# PowerSupply-5V-3_3V-v11-OtherMill.net
KiCad netlist of a schematic drawn in EAGLE
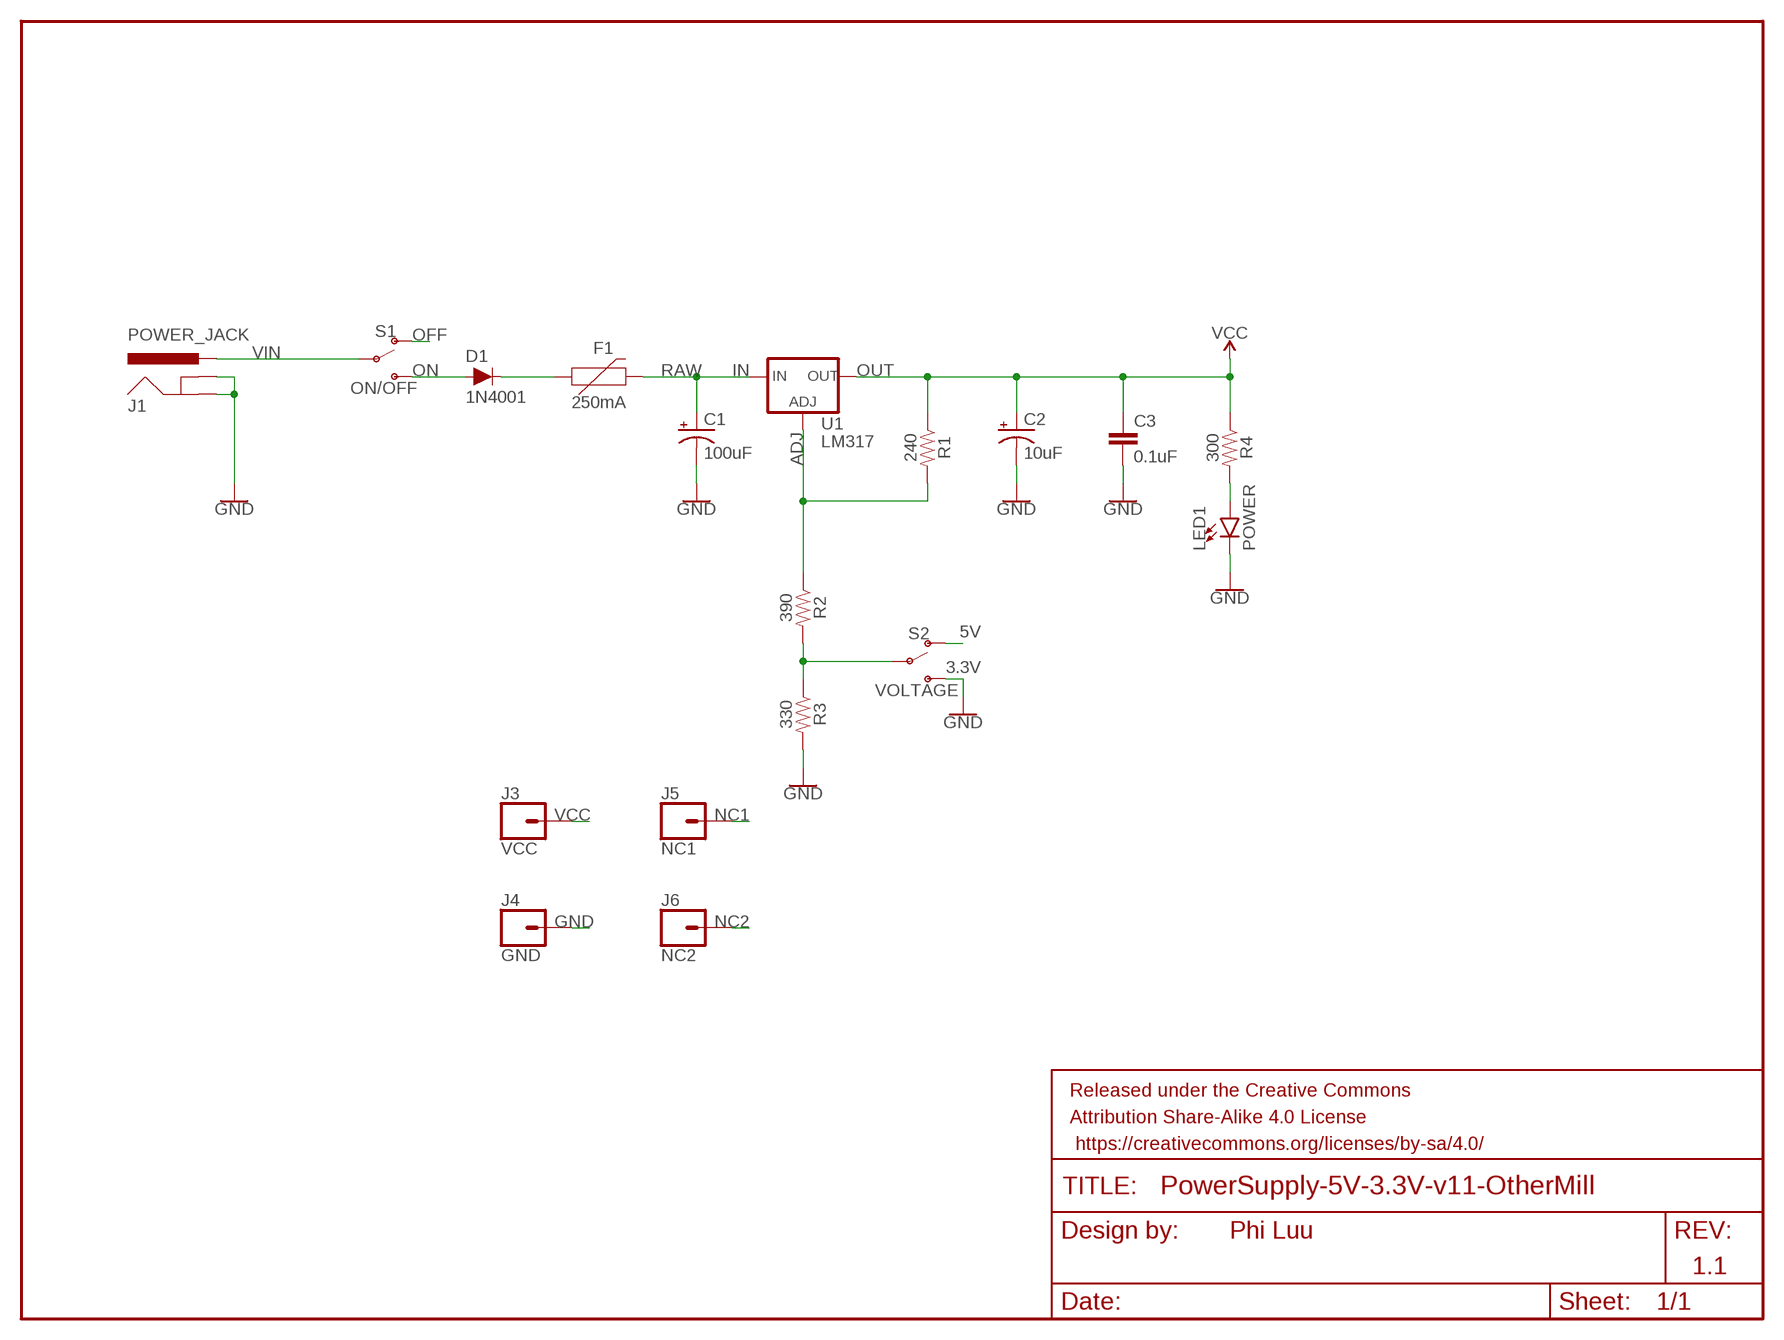
[diagram p0: schematic, sheet 1]

(export (version "E")
  (design (tool "Eeschema 10.0.6"))
  (components
    (comp (ref "C1")
      (value "100uF")
      (footprint "eagle-import:CPOL-RADIAL-2.5MM-6.5MM")
      (libsource (lib "eagle-import") (part "100UF-POLAR-RADIAL-2.5MM-25V-20%"))
    )
    (comp (ref "C2")
      (value "10uF")
      (footprint "eagle-import:CPOL-RADIAL-2.5MM-5MM")
      (libsource (lib "eagle-import") (part "10UF-POLAR-RADIAL-2.5MM-25V-20%"))
    )
    (comp (ref "C3")
      (value "0.1uF")
      (footprint "eagle-import:CAP-PTH-SMALL-KIT")
      (libsource (lib "eagle-import") (part "0.1UF-KIT-EZ-50V-20%"))
    )
    (comp (ref "D1")
      (value "1N4001")
      (footprint "eagle-import:DIODE-1N4001")
      (libsource (lib "eagle-import") (part "DIODE-PTH"))
    )
    (comp (ref "F1")
      (value "250mA")
      (footprint "eagle-import:PTH")
      (libsource (lib "eagle-import") (part "PPTC_PTH"))
    )
    (comp (ref "FRAME1")
      (value "FRAME-LETTER")
      (footprint "eagle-import:CREATIVE_COMMONS")
      (libsource (lib "eagle-import") (part "FRAME-LETTER"))
    )
    (comp (ref "J1")
      (value "POWER_JACK")
      (footprint "eagle-import:POWER_JACK_PTH")
      (libsource (lib "eagle-import") (part "POWER_JACK"))
    )
    (comp (ref "J3")
      (value "VCC")
      (footprint "eagle-import:1X01")
      (libsource (lib "eagle-import") (part "CONN_01"))
    )
    (comp (ref "J4")
      (value "GND")
      (footprint "eagle-import:1X01")
      (libsource (lib "eagle-import") (part "CONN_01"))
    )
    (comp (ref "J5")
      (value "NC1")
      (footprint "eagle-import:1X01")
      (libsource (lib "eagle-import") (part "CONN_01"))
    )
    (comp (ref "J6")
      (value "NC2")
      (footprint "eagle-import:1X01")
      (libsource (lib "eagle-import") (part "CONN_01"))
    )
    (comp (ref "LED1")
      (value "POWER")
      (footprint "eagle-import:LED_5MM")
      (libsource (lib "eagle-import") (part "LED5MM"))
    )
    (comp (ref "R1")
      (value "240")
      (footprint "eagle-import:AXIAL-0.3")
      (libsource (lib "eagle-import") (part "1KOHM-HORIZ-1/4W-5%"))
    )
    (comp (ref "R2")
      (value "390")
      (footprint "eagle-import:AXIAL-0.3")
      (libsource (lib "eagle-import") (part "1KOHM-HORIZ-1/4W-5%"))
    )
    (comp (ref "R3")
      (value "330")
      (footprint "eagle-import:AXIAL-0.3")
      (libsource (lib "eagle-import") (part "1KOHM-HORIZ-1/4W-5%"))
    )
    (comp (ref "R4")
      (value "300")
      (footprint "eagle-import:AXIAL-0.3")
      (libsource (lib "eagle-import") (part "1KOHM-HORIZ-1/4W-5%"))
    )
    (comp (ref "S1")
      (value "ON/OFF")
      (footprint "eagle-import:SWITCH_SPDT_PTH_11.6X4.0MM")
      (libsource (lib "eagle-import") (part "SWITCH-SPDT-PTH-11.6X4.0MM"))
    )
    (comp (ref "S2")
      (value "VOLTAGE")
      (footprint "eagle-import:SWITCH_SPDT_PTH_11.6X4.0MM")
      (libsource (lib "eagle-import") (part "SWITCH-SPDT-PTH-11.6X4.0MM"))
    )
    (comp (ref "U1")
      (value "LM317")
      (footprint "eagle-import:TO220-ADJ")
      (libsource (lib "eagle-import") (part "V_REG_317SINK"))
    )
  )
  (nets
    (net (code "1") (name "/5V") (class "Default")
      (node (ref "S2") (pin "1") (pinfunction "O_1") (pintype "passive"))
    )
    (net (code "2") (name "/ADJ") (class "Default")
      (node (ref "R1") (pin "P$2") (pinfunction "2_P$2") (pintype "passive"))
      (node (ref "R2") (pin "P$1") (pinfunction "1_P$1") (pintype "passive"))
      (node (ref "U1") (pin "ADJ") (pinfunction "ADJ_ADJ") (pintype "input"))
    )
    (net (code "3") (name "/NC1") (class "Default")
      (node (ref "J5") (pin "1") (pinfunction "1_1") (pintype "passive"))
    )
    (net (code "4") (name "/NC2") (class "Default")
      (node (ref "J6") (pin "1") (pinfunction "1_1") (pintype "passive"))
    )
    (net (code "5") (name "/OFF") (class "Default")
      (node (ref "S1") (pin "1") (pinfunction "O_1") (pintype "passive"))
    )
    (net (code "6") (name "/ON") (class "Default")
      (node (ref "D1") (pin "A") (pinfunction "A_A") (pintype "passive"))
      (node (ref "S1") (pin "3") (pinfunction "S_3") (pintype "passive"))
    )
    (net (code "7") (name "/RAW") (class "Default")
      (node (ref "C1") (pin "1") (pinfunction "+_1") (pintype "passive"))
      (node (ref "F1") (pin "P$2") (pinfunction "2_P$2") (pintype "bidirectional"))
      (node (ref "U1") (pin "IN") (pinfunction "IN_IN") (pintype "input"))
    )
    (net (code "8") (name "/VIN") (class "Default")
      (node (ref "J1") (pin "PWR") (pinfunction "PWR_PWR") (pintype "bidirectional"))
      (node (ref "S1") (pin "2") (pinfunction "P_2") (pintype "passive"))
    )
    (net (code "9") (name "GND") (class "Default")
      (node (ref "C1") (pin "2") (pinfunction "-_2") (pintype "passive"))
      (node (ref "C2") (pin "2") (pinfunction "-_2") (pintype "passive"))
      (node (ref "C3") (pin "2") (pinfunction "2_2") (pintype "passive"))
      (node (ref "J1") (pin "GND") (pinfunction "GND_GND") (pintype "bidirectional"))
      (node (ref "J1") (pin "GNDBREAK") (pinfunction "GNDBREAK_GNDBREAK") (pintype "bidirectional"))
      (node (ref "J4") (pin "1") (pinfunction "1_1") (pintype "passive"))
      (node (ref "LED1") (pin "K") (pinfunction "C_K") (pintype "passive"))
      (node (ref "R3") (pin "P$2") (pinfunction "2_P$2") (pintype "passive"))
      (node (ref "S2") (pin "3") (pinfunction "S_3") (pintype "passive"))
    )
    (net (code "10") (name "Net-(F1-1)") (class "Default")
      (node (ref "D1") (pin "C") (pinfunction "C_C") (pintype "passive"))
      (node (ref "F1") (pin "P$1") (pinfunction "1_P$1") (pintype "bidirectional"))
    )
    (net (code "11") (name "Net-(R2-2)") (class "Default")
      (node (ref "R2") (pin "P$2") (pinfunction "2_P$2") (pintype "passive"))
      (node (ref "R3") (pin "P$1") (pinfunction "1_P$1") (pintype "passive"))
      (node (ref "S2") (pin "2") (pinfunction "P_2") (pintype "passive"))
    )
    (net (code "12") (name "Net-(R4-2)") (class "Default")
      (node (ref "LED1") (pin "A") (pinfunction "A_A") (pintype "passive"))
      (node (ref "R4") (pin "P$2") (pinfunction "2_P$2") (pintype "passive"))
    )
    (net (code "13") (name "VCC") (class "Default")
      (node (ref "C2") (pin "1") (pinfunction "+_1") (pintype "passive"))
      (node (ref "C3") (pin "1") (pinfunction "1_1") (pintype "passive"))
      (node (ref "J3") (pin "1") (pinfunction "1_1") (pintype "passive"))
      (node (ref "R1") (pin "P$1") (pinfunction "1_P$1") (pintype "passive"))
      (node (ref "R4") (pin "P$1") (pinfunction "1_P$1") (pintype "passive"))
      (node (ref "U1") (pin "OUT") (pinfunction "OUT_OUT") (pintype "output"))
    )
  )
)
